# Sheet2.net
KiCad netlist of a schematic drawn in Altium Designer
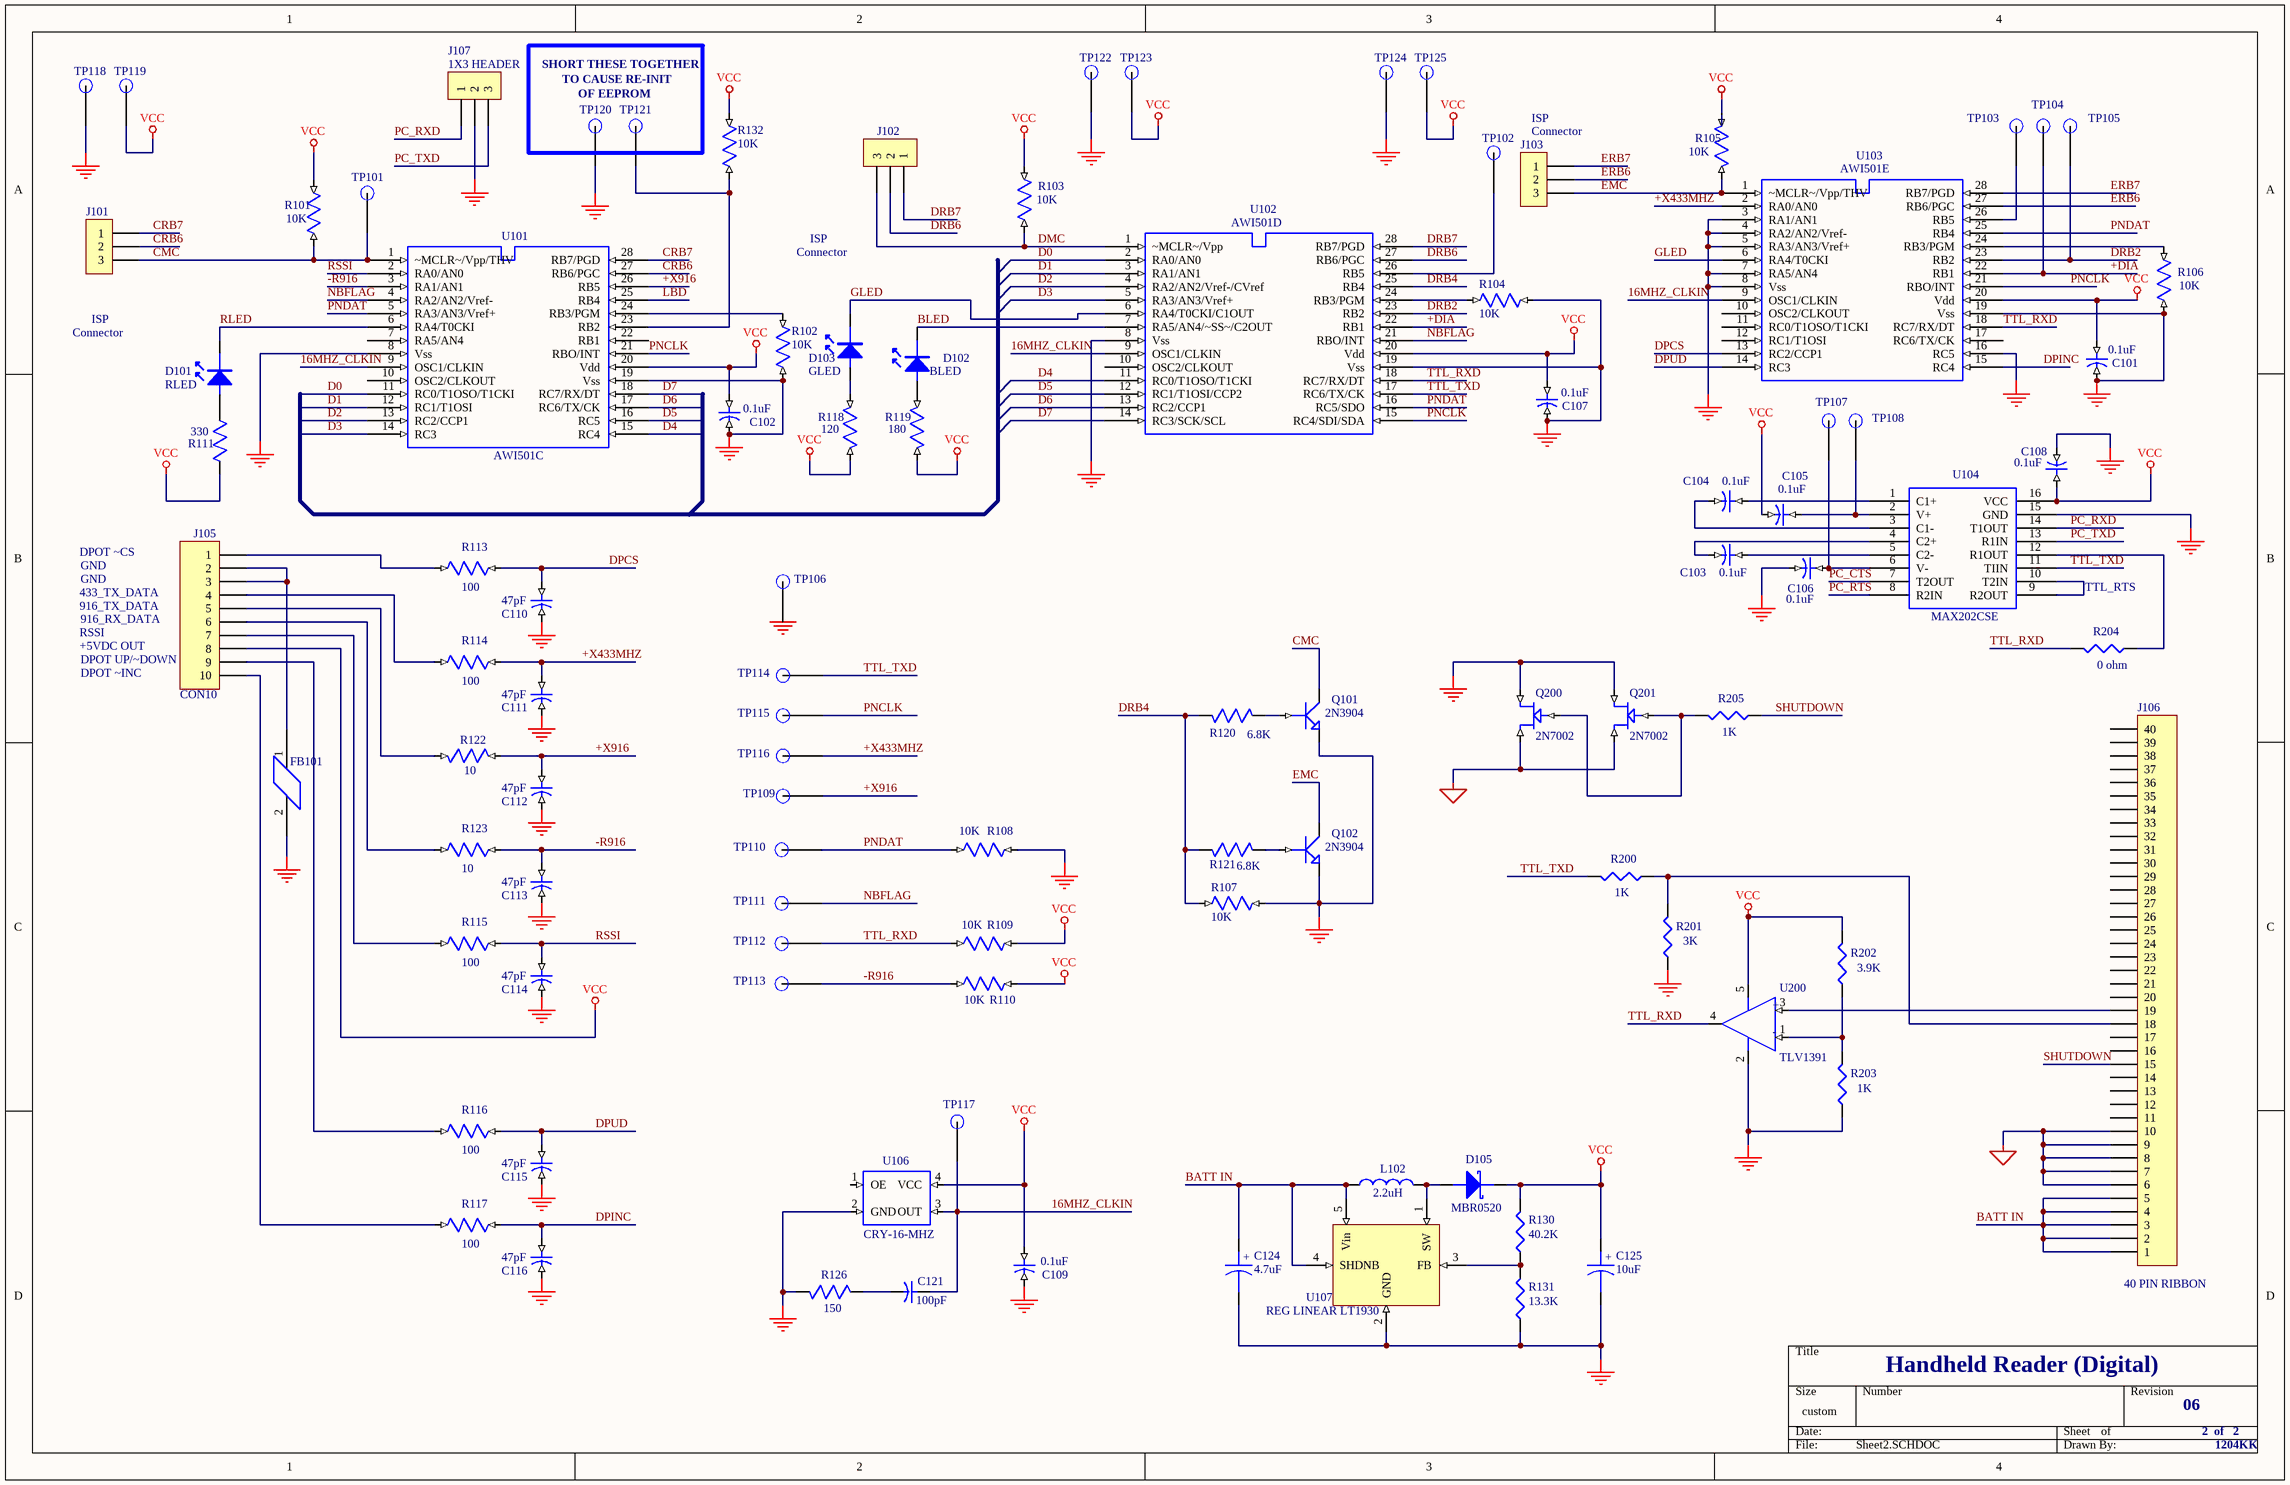
[diagram p0: Sheet2.SCHDOC]

(export (version "E")
  (design (tool "Eeschema 10.0.6"))
  (components
    (comp (ref "C101") (value "0.1uF") (footprint "0603") (libsource (lib "") (part "C_603_1")))
    (comp (ref "C102") (value "0.1uF") (footprint "0603") (libsource (lib "") (part "C_603_1")))
    (comp (ref "C103") (value "0.1uF") (footprint "0603") (libsource (lib "*") (part "C_603")))
    (comp (ref "C104") (value "0.1uF") (footprint "0603") (libsource (lib "*") (part "C_603")))
    (comp (ref "C105") (value "0.1uF") (footprint "0603") (libsource (lib "*") (part "C_603")))
    (comp (ref "C106") (value "0.1uF") (footprint "0603") (libsource (lib "*") (part "C_603")))
    (comp (ref "C107") (value "0.1uF") (footprint "0603") (libsource (lib "") (part "C_603_1")))
    (comp (ref "C108") (value "0.1uF") (footprint "0603") (libsource (lib "*") (part "C_603")))
    (comp (ref "C109") (value "0.1uF") (footprint "0603") (libsource (lib "*") (part "C_603")))
    (comp (ref "C110") (value "47pF") (footprint "0603") (libsource (lib "*") (part "C0603")))
    (comp (ref "C111") (value "47pF") (footprint "0603") (libsource (lib "*") (part "C0603")))
    (comp (ref "C112") (value "47pF") (footprint "0603") (libsource (lib "*") (part "C0603")))
    (comp (ref "C113") (value "47pF") (footprint "0603") (libsource (lib "*") (part "C0603")))
    (comp (ref "C114") (value "47pF") (footprint "0603") (libsource (lib "*") (part "C0603")))
    (comp (ref "C115") (value "47pF") (footprint "0603") (libsource (lib "*") (part "C0603")))
    (comp (ref "C116") (value "47pF") (footprint "0603") (libsource (lib "*") (part "C0603")))
    (comp (ref "C121") (value "100pF") (footprint "0603") (libsource (lib "*") (part "C_0603")))
    (comp (ref "C124")
      (value "4.7uF")
      (footprint "CAP A CASE")
      (description "Capacitor")
      (libsource (lib "*") (part "CAPACITOR POL"))
    )
    (comp (ref "C125")
      (value "10uF")
      (footprint "CAP A CASE")
      (description "Capacitor")
      (libsource (lib "*") (part "CAPACITOR POL"))
    )
    (comp (ref "D101") (value "RLED") (footprint "SOD123 DIODE") (libsource (lib "*") (part "LED")))
    (comp (ref "D102") (value "BLED") (footprint "SOD123 DIODE") (libsource (lib "*") (part "LED")))
    (comp (ref "D103") (value "GLED") (footprint "SOD123 DIODE") (libsource (lib "*") (part "LED")))
    (comp (ref "D105")
      (value "MBR0520")
      (footprint "SOD123")
      (description "Schottky Diode")
      (libsource (lib "*") (part "DIODE SCHOTTKY"))
    )
    (comp (ref "FB101") (value "FB 0603") (footprint "0603") (libsource (lib "*") (part "FB_0603")))
    (comp (ref "J101")
      (value "1X3 HEADER")
      (footprint "1X3 HEADER")
      (description "Connector")
      (libsource (lib "*") (part "CON3"))
    )
    (comp (ref "J102")
      (value "1X3 HEADER")
      (footprint "1X3 HEADER")
      (description "Connector")
      (libsource (lib "") (part "CON3_1"))
    )
    (comp (ref "J103")
      (value "1X3 HEADER")
      (footprint "1X3 HEADER")
      (description "Connector")
      (libsource (lib "*") (part "CON3"))
    )
    (comp (ref "J105")
      (value "CON10")
      (footprint "1X10 HEADER SPECIAL")
      (description "Connector")
      (libsource (lib "*") (part "CON10"))
    )
    (comp (ref "J106")
      (value "40 PIN RIBBON")
      (footprint "40 PIN RIBBON CONN")
      (description "Connector")
      (libsource (lib "*") (part "CON40"))
    )
    (comp (ref "J107")
      (value "1X3 HEADER")
      (footprint "1X3 HEADER")
      (description "Connector")
      (libsource (lib "") (part "CON3_2"))
    )
    (comp (ref "L102")
      (value "2.2uH")
      (footprint "COIL BOURNS SDR7030-330M")
      (libsource (lib "*") (part "INDUCTOR1"))
    )
    (comp (ref "Q101")
      (value "2N3904")
      (footprint "SOT23 TRANS")
      (description "NPN Transistor")
      (libsource (lib "*") (part "NPN1"))
    )
    (comp (ref "Q102")
      (value "2N3904")
      (footprint "SOT23 TRANS")
      (description "NPN Transistor")
      (libsource (lib "*") (part "NPN1"))
    )
    (comp (ref "Q200") (value "2N7002") (footprint "SOT23 FET") (libsource (lib "*") (part "JFET N")))
    (comp (ref "Q201") (value "2N7002") (footprint "SOT23 FET") (libsource (lib "*") (part "JFET N")))
    (comp (ref "R101") (value "10K") (footprint "0603") (libsource (lib "*") (part "R_603")))
    (comp (ref "R102") (value "10K") (footprint "0603") (libsource (lib "*") (part "R_603")))
    (comp (ref "R103") (value "10K") (footprint "0603") (libsource (lib "*") (part "R_603")))
    (comp (ref "R104") (value "10K") (footprint "0603") (libsource (lib "*") (part "R_603")))
    (comp (ref "R105") (value "10K") (footprint "0603") (libsource (lib "*") (part "R_603")))
    (comp (ref "R106") (value "10K") (footprint "0603") (libsource (lib "*") (part "R_603")))
    (comp (ref "R107") (value "10K") (footprint "0603") (libsource (lib "*") (part "R_603")))
    (comp (ref "R108") (value "10K") (footprint "0603") (libsource (lib "*") (part "R_603")))
    (comp (ref "R109") (value "10K") (footprint "0603") (libsource (lib "*") (part "R_603")))
    (comp (ref "R110") (value "10K") (footprint "0603") (libsource (lib "*") (part "R_603")))
    (comp (ref "R111") (value "330") (footprint "0603") (libsource (lib "*") (part "R_0603")))
    (comp (ref "R113") (value "100") (footprint "0603") (libsource (lib "*") (part "R0603")))
    (comp (ref "R114") (value "100") (footprint "0603") (libsource (lib "*") (part "R0603")))
    (comp (ref "R115") (value "100") (footprint "0603") (libsource (lib "*") (part "R0603")))
    (comp (ref "R116") (value "100") (footprint "0603") (libsource (lib "*") (part "R0603")))
    (comp (ref "R117") (value "100") (footprint "0603") (libsource (lib "*") (part "R0603")))
    (comp (ref "R118") (value "120") (footprint "0603") (libsource (lib "*") (part "R0402")))
    (comp (ref "R119") (value "180") (footprint "0603") (libsource (lib "*") (part "R0402")))
    (comp (ref "R120") (value "6.8K") (footprint "0603") (libsource (lib "*") (part "R_0603")))
    (comp (ref "R121") (value "6.8K") (footprint "0603") (libsource (lib "*") (part "R_0603")))
    (comp (ref "R122") (value "10") (footprint "0603") (libsource (lib "*") (part "R_603")))
    (comp (ref "R123") (value "10") (footprint "0603") (libsource (lib "*") (part "R0603")))
    (comp (ref "R126") (value "150") (footprint "0603") (libsource (lib "*") (part "R_0603")))
    (comp (ref "R130") (value "40.2K") (footprint "0603") (libsource (lib "*") (part "RES1")))
    (comp (ref "R131") (value "13.3K") (footprint "0603") (libsource (lib "*") (part "RES1")))
    (comp (ref "R132") (value "10K") (footprint "0603") (libsource (lib "*") (part "R_603")))
    (comp (ref "R200") (value "1K") (footprint "0603") (libsource (lib "*") (part "RES1")))
    (comp (ref "R201") (value "3K") (footprint "0603") (libsource (lib "*") (part "RES1")))
    (comp (ref "R202") (value "3.9K") (footprint "0603") (libsource (lib "*") (part "RES1")))
    (comp (ref "R203") (value "1K") (footprint "0603") (libsource (lib "*") (part "RES1")))
    (comp (ref "R204") (value "0 ohm") (footprint "0603") (libsource (lib "*") (part "RES1")))
    (comp (ref "R205") (value "1K") (footprint "0603") (libsource (lib "*") (part "RES1")))
    (comp (ref "TP101") (value "TP") (footprint "TEST POINT PAD") (libsource (lib "*") (part "TESTPOINT_1")))
    (comp (ref "TP102") (value "TP") (footprint "TEST POINT PAD") (libsource (lib "*") (part "TESTPOINT_1")))
    (comp (ref "TP103") (value "TP") (footprint "TEST POINT PAD") (libsource (lib "*") (part "TESTPOINT_1")))
    (comp (ref "TP104") (value "TP") (footprint "TEST POINT PAD") (libsource (lib "*") (part "TESTPOINT_1")))
    (comp (ref "TP105") (value "TP") (footprint "TEST POINT PAD") (libsource (lib "*") (part "TESTPOINT_1")))
    (comp (ref "TP106") (value "TP") (footprint "TEST POINT PAD") (libsource (lib "*") (part "TESTPOINT_1")))
    (comp (ref "TP107") (value "TP") (footprint "TEST POINT PAD") (libsource (lib "*") (part "TESTPOINT_1")))
    (comp (ref "TP108") (value "TP") (footprint "TEST POINT PAD") (libsource (lib "*") (part "TESTPOINT_1")))
    (comp (ref "TP109") (value "TP") (footprint "TEST POINT PAD") (libsource (lib "*") (part "TESTPOINT_1")))
    (comp (ref "TP110") (value "TP") (footprint "TEST POINT PAD") (libsource (lib "*") (part "TESTPOINT_1")))
    (comp (ref "TP111") (value "TP") (footprint "TEST POINT PAD") (libsource (lib "*") (part "TESTPOINT_1")))
    (comp (ref "TP112") (value "TP") (footprint "TEST POINT PAD") (libsource (lib "*") (part "TESTPOINT_1")))
    (comp (ref "TP113") (value "TP") (footprint "TEST POINT PAD") (libsource (lib "*") (part "TESTPOINT_1")))
    (comp (ref "TP114") (value "TP") (footprint "TEST POINT PAD") (libsource (lib "*") (part "TESTPOINT_1")))
    (comp (ref "TP115") (value "TP") (footprint "TEST POINT PAD") (libsource (lib "*") (part "TESTPOINT_1")))
    (comp (ref "TP116") (value "TP") (footprint "TEST POINT PAD") (libsource (lib "*") (part "TESTPOINT_1")))
    (comp (ref "TP117") (value "TP") (footprint "TEST POINT PAD") (libsource (lib "*") (part "TESTPOINT_1")))
    (comp (ref "TP118") (value "TP") (footprint "TEST POINT PAD") (libsource (lib "*") (part "TESTPOINT_1")))
    (comp (ref "TP119") (value "TP") (footprint "TEST POINT PAD") (libsource (lib "*") (part "TESTPOINT_1")))
    (comp (ref "TP120") (value "TP") (footprint "TEST POINT PAD") (libsource (lib "*") (part "TESTPOINT_1")))
    (comp (ref "TP121") (value "TP") (footprint "TEST POINT PAD") (libsource (lib "*") (part "TESTPOINT_1")))
    (comp (ref "TP122") (value "TP") (footprint "TEST POINT PAD") (libsource (lib "*") (part "TESTPOINT_1")))
    (comp (ref "TP123") (value "TP") (footprint "TEST POINT PAD") (libsource (lib "*") (part "TESTPOINT_1")))
    (comp (ref "TP124") (value "TP") (footprint "TEST POINT PAD") (libsource (lib "*") (part "TESTPOINT_1")))
    (comp (ref "TP125") (value "TP") (footprint "TEST POINT PAD") (libsource (lib "*") (part "TESTPOINT_1")))
    (comp (ref "U101") (value "AWI501C") (footprint "SSOP28") (libsource (lib "*") (part "PIC16F870")))
    (comp (ref "U102") (value "AWI501D") (footprint "SSOP28") (libsource (lib "*") (part "PIC16F876A")))
    (comp (ref "U103") (value "AWI501E") (footprint "SSOP28") (libsource (lib "*") (part "PIC16F870")))
    (comp (ref "U104") (value "MAX202CSE") (footprint "SO16") (libsource (lib "*") (part "MAX202CSE")))
    (comp (ref "U106")
      (value "CRY-16-MHZ")
      (footprint "SMT OSCILLATOR")
      (libsource (lib "*") (part "CRY-SMD-5-7"))
    )
    (comp (ref "U107")
      (value "REG LINEAR LT1930")
      (footprint "SOT23-5A")
      (libsource (lib "*") (part "REG LINEAR LT1930"))
    )
    (comp (ref "U200") (value "TLV1391") (footprint "SOT25") (libsource (lib "*") (part "TLV1391")))
  )
  (nets
    (net (code "1") (name "/+DIA") (class "Default")
      (node (ref "TP104") (pin "1") (pinfunction "TP_1") (pintype "passive"))
      (node (ref "U102") (pin "22") (pinfunction "RB1_22") (pintype "input"))
      (node (ref "U103") (pin "22") (pinfunction "RB1_22") (pintype "input"))
    )
    (net (code "2") (name "/+X433MHZ") (class "Default")
      (node (ref "C111") (pin "1") (pinfunction "A_1") (pintype "input"))
      (node (ref "R114") (pin "2") (pinfunction "B_2") (pintype "input"))
      (node (ref "TP116") (pin "1") (pinfunction "TP_1") (pintype "passive"))
      (node (ref "U103") (pin "2") (pinfunction "RA0/AN0_2") (pintype "input"))
    )
    (net (code "3") (name "/+X916") (class "Default")
      (node (ref "C112") (pin "1") (pinfunction "A_1") (pintype "input"))
      (node (ref "R122") (pin "1") (pinfunction "A_1") (pintype "input"))
      (node (ref "TP109") (pin "1") (pinfunction "TP_1") (pintype "passive"))
      (node (ref "U101") (pin "26") (pinfunction "RB5_26") (pintype "input"))
    )
    (net (code "4") (name "/-R916") (class "Default")
      (node (ref "C113") (pin "1") (pinfunction "A_1") (pintype "input"))
      (node (ref "R110") (pin "2") (pinfunction "B_2") (pintype "input"))
      (node (ref "R123") (pin "2") (pinfunction "B_2") (pintype "input"))
      (node (ref "TP113") (pin "1") (pinfunction "TP_1") (pintype "passive"))
      (node (ref "U101") (pin "3") (pinfunction "RA1/AN1_3") (pintype "input"))
    )
    (net (code "5") (name "/16MHZ_CLKIN") (class "Default")
      (node (ref "C121") (pin "1") (pinfunction "A_1") (pintype "passive"))
      (node (ref "TP117") (pin "1") (pinfunction "TP_1") (pintype "passive"))
      (node (ref "U101") (pin "9") (pinfunction "OSC1/CLKIN_9") (pintype "input"))
      (node (ref "U102") (pin "9") (pinfunction "OSC1/CLKIN_9") (pintype "input"))
      (node (ref "U103") (pin "9") (pinfunction "OSC1/CLKIN_9") (pintype "input"))
      (node (ref "U106") (pin "3") (pinfunction "OUT_3") (pintype "input"))
    )
    (net (code "6") (name "/BATT IN") (class "Default")
      (node (ref "C124") (pin "1") (pinfunction "1_1") (pintype "passive"))
      (node (ref "J106") (pin "1") (pinfunction "1_1") (pintype "passive"))
      (node (ref "J106") (pin "2") (pinfunction "2_2") (pintype "passive"))
      (node (ref "J106") (pin "3") (pinfunction "3_3") (pintype "passive"))
      (node (ref "J106") (pin "4") (pinfunction "4_4") (pintype "passive"))
      (node (ref "J106") (pin "5") (pinfunction "5_5") (pintype "passive"))
      (node (ref "L102") (pin "1") (pinfunction "1_1") (pintype "passive"))
      (node (ref "U107") (pin "4") (pinfunction "SHDNB_4") (pintype "input"))
      (node (ref "U107") (pin "5") (pinfunction "Vin_5") (pintype "input"))
    )
    (net (code "7") (name "/BLED") (class "Default")
      (node (ref "D102") (pin "K") (pinfunction "K_K") (pintype "passive"))
      (node (ref "U102") (pin "7") (pinfunction "RA5/AN4/~SS~/C2OUT_7") (pintype "input"))
    )
    (net (code "8") (name "/CMC") (class "Default")
      (node (ref "J101") (pin "3") (pinfunction "3_3") (pintype "passive"))
      (node (ref "Q101") (pin "C") (pinfunction "C_C") (pintype "passive"))
      (node (ref "R101") (pin "2") (pinfunction "B_2") (pintype "input"))
      (node (ref "TP101") (pin "1") (pinfunction "TP_1") (pintype "passive"))
      (node (ref "U101") (pin "1") (pinfunction "~MCLR~/Vpp/THV_1") (pintype "input"))
    )
    (net (code "9") (name "/CRB6") (class "Default")
      (node (ref "J101") (pin "2") (pinfunction "2_2") (pintype "passive"))
      (node (ref "U101") (pin "27") (pinfunction "RB6/PGC_27") (pintype "input"))
    )
    (net (code "10") (name "/CRB7") (class "Default")
      (node (ref "J101") (pin "1") (pinfunction "1_1") (pintype "passive"))
      (node (ref "U101") (pin "28") (pinfunction "RB7/PGD_28") (pintype "input"))
    )
    (net (code "11") (name "/D0") (class "Default")
      (node (ref "U101") (pin "11") (pinfunction "RC0/T1OSO/T1CKI_11") (pintype "input"))
      (node (ref "U102") (pin "2") (pinfunction "RA0/AN0_2") (pintype "input"))
    )
    (net (code "12") (name "/D1") (class "Default")
      (node (ref "U101") (pin "12") (pinfunction "RC1/T1OSI_12") (pintype "input"))
      (node (ref "U102") (pin "3") (pinfunction "RA1/AN1_3") (pintype "input"))
    )
    (net (code "13") (name "/D2") (class "Default")
      (node (ref "U101") (pin "13") (pinfunction "RC2/CCP1_13") (pintype "input"))
      (node (ref "U102") (pin "4") (pinfunction "RA2/AN2/Vref-/CVref_4") (pintype "input"))
    )
    (net (code "14") (name "/D3") (class "Default")
      (node (ref "U101") (pin "14") (pinfunction "RC3_14") (pintype "input"))
      (node (ref "U102") (pin "5") (pinfunction "RA3/AN3/Vref+_5") (pintype "input"))
    )
    (net (code "15") (name "/D4") (class "Default")
      (node (ref "U101") (pin "15") (pinfunction "RC4_15") (pintype "input"))
      (node (ref "U102") (pin "11") (pinfunction "RC0/T1OSO/T1CKI_11") (pintype "input"))
    )
    (net (code "16") (name "/D5") (class "Default")
      (node (ref "U101") (pin "16") (pinfunction "RC5_16") (pintype "input"))
      (node (ref "U102") (pin "12") (pinfunction "RC1/T1OSI/CCP2_12") (pintype "input"))
    )
    (net (code "17") (name "/D6") (class "Default")
      (node (ref "U101") (pin "17") (pinfunction "RC6/TX/CK_17") (pintype "input"))
      (node (ref "U102") (pin "13") (pinfunction "RC2/CCP1_13") (pintype "input"))
    )
    (net (code "18") (name "/D7") (class "Default")
      (node (ref "U101") (pin "18") (pinfunction "RC7/RX/DT_18") (pintype "input"))
      (node (ref "U102") (pin "14") (pinfunction "RC3/SCK/SCL_14") (pintype "input"))
    )
    (net (code "19") (name "/DMC") (class "Default")
      (node (ref "J102") (pin "3") (pinfunction "3_3") (pintype "passive"))
      (node (ref "R103") (pin "2") (pinfunction "B_2") (pintype "input"))
      (node (ref "U102") (pin "1") (pinfunction "~MCLR~/Vpp_1") (pintype "input"))
    )
    (net (code "20") (name "/DPCS") (class "Default")
      (node (ref "C110") (pin "1") (pinfunction "A_1") (pintype "input"))
      (node (ref "R113") (pin "2") (pinfunction "B_2") (pintype "input"))
      (node (ref "U103") (pin "13") (pinfunction "RC2/CCP1_13") (pintype "input"))
    )
    (net (code "21") (name "/DPINC") (class "Default")
      (node (ref "C116") (pin "1") (pinfunction "A_1") (pintype "input"))
      (node (ref "R117") (pin "2") (pinfunction "B_2") (pintype "input"))
      (node (ref "U103") (pin "15") (pinfunction "RC4_15") (pintype "input"))
    )
    (net (code "22") (name "/DPUD") (class "Default")
      (node (ref "C115") (pin "1") (pinfunction "A_1") (pintype "input"))
      (node (ref "R116") (pin "2") (pinfunction "B_2") (pintype "input"))
      (node (ref "U103") (pin "14") (pinfunction "RC3_14") (pintype "input"))
    )
    (net (code "23") (name "/DRB2") (class "Default")
      (node (ref "TP105") (pin "1") (pinfunction "TP_1") (pintype "passive"))
      (node (ref "U102") (pin "23") (pinfunction "RB2_23") (pintype "input"))
      (node (ref "U103") (pin "23") (pinfunction "RB2_23") (pintype "input"))
    )
    (net (code "24") (name "/DRB4") (class "Default")
      (node (ref "R107") (pin "1") (pinfunction "A_1") (pintype "input"))
      (node (ref "R120") (pin "1") (pinfunction "A_1") (pintype "passive"))
      (node (ref "R121") (pin "1") (pinfunction "A_1") (pintype "passive"))
      (node (ref "U102") (pin "25") (pinfunction "RB4_25") (pintype "input"))
    )
    (net (code "25") (name "/DRB6") (class "Default")
      (node (ref "J102") (pin "2") (pinfunction "2_2") (pintype "passive"))
      (node (ref "U102") (pin "27") (pinfunction "RB6/PGC_27") (pintype "input"))
    )
    (net (code "26") (name "/DRB7") (class "Default")
      (node (ref "J102") (pin "1") (pinfunction "1_1") (pintype "passive"))
      (node (ref "U102") (pin "28") (pinfunction "RB7/PGD_28") (pintype "input"))
    )
    (net (code "27") (name "/EMC") (class "Default")
      (node (ref "J103") (pin "3") (pinfunction "3_3") (pintype "passive"))
      (node (ref "Q102") (pin "C") (pinfunction "C_C") (pintype "passive"))
      (node (ref "R105") (pin "2") (pinfunction "B_2") (pintype "input"))
      (node (ref "U103") (pin "1") (pinfunction "~MCLR~/Vpp/THV_1") (pintype "input"))
    )
    (net (code "28") (name "/ERB6") (class "Default")
      (node (ref "J103") (pin "2") (pinfunction "2_2") (pintype "passive"))
      (node (ref "U103") (pin "27") (pinfunction "RB6/PGC_27") (pintype "input"))
    )
    (net (code "29") (name "/ERB7") (class "Default")
      (node (ref "J103") (pin "1") (pinfunction "1_1") (pintype "passive"))
      (node (ref "U103") (pin "28") (pinfunction "RB7/PGD_28") (pintype "input"))
    )
    (net (code "30") (name "/GLED") (class "Default")
      (node (ref "D103") (pin "K") (pinfunction "K_K") (pintype "passive"))
      (node (ref "U102") (pin "6") (pinfunction "RA4/T0CKI/C1OUT_6") (pintype "input"))
      (node (ref "U103") (pin "6") (pinfunction "RA4/T0CKI_6") (pintype "input"))
    )
    (net (code "31") (name "/LBD") (class "Default")
      (node (ref "U101") (pin "25") (pinfunction "RB4_25") (pintype "input"))
    )
    (net (code "32") (name "/NBFLAG") (class "Default")
      (node (ref "TP111") (pin "1") (pinfunction "TP_1") (pintype "passive"))
      (node (ref "U101") (pin "4") (pinfunction "RA2/AN2/Vref-_4") (pintype "input"))
      (node (ref "U102") (pin "21") (pinfunction "RBO/INT_21") (pintype "input"))
    )
    (net (code "33") (name "/PC_CTS") (class "Default")
      (node (ref "U104") (pin "7") (pinfunction "T2OUT_7") (pintype "passive"))
    )
    (net (code "34") (name "/PC_RTS") (class "Default")
      (node (ref "U104") (pin "8") (pinfunction "R2IN_8") (pintype "passive"))
    )
    (net (code "35") (name "/PC_RXD") (class "Default")
      (node (ref "J107") (pin "1") (pinfunction "1_1") (pintype "passive"))
      (node (ref "U104") (pin "14") (pinfunction "T1OUT_14") (pintype "passive"))
    )
    (net (code "36") (name "/PC_TXD") (class "Default")
      (node (ref "J107") (pin "3") (pinfunction "3_3") (pintype "passive"))
      (node (ref "U104") (pin "13") (pinfunction "R1IN_13") (pintype "passive"))
    )
    (net (code "37") (name "/PNCLK") (class "Default")
      (node (ref "TP115") (pin "1") (pinfunction "TP_1") (pintype "passive"))
      (node (ref "U101") (pin "21") (pinfunction "RBO/INT_21") (pintype "input"))
      (node (ref "U102") (pin "15") (pinfunction "RC4/SDI/SDA_15") (pintype "input"))
      (node (ref "U103") (pin "21") (pinfunction "RBO/INT_21") (pintype "input"))
    )
    (net (code "38") (name "/PNDAT") (class "Default")
      (node (ref "R108") (pin "2") (pinfunction "B_2") (pintype "input"))
      (node (ref "TP110") (pin "1") (pinfunction "TP_1") (pintype "passive"))
      (node (ref "U101") (pin "5") (pinfunction "RA3/AN3/Vref+_5") (pintype "input"))
      (node (ref "U102") (pin "16") (pinfunction "RC5/SDO_16") (pintype "input"))
      (node (ref "U103") (pin "25") (pinfunction "RB4_25") (pintype "input"))
    )
    (net (code "39") (name "/RLED") (class "Default")
      (node (ref "D101") (pin "K") (pinfunction "K_K") (pintype "passive"))
      (node (ref "U101") (pin "6") (pinfunction "RA4/T0CKI_6") (pintype "input"))
    )
    (net (code "40") (name "/RSSI") (class "Default")
      (node (ref "C114") (pin "1") (pinfunction "A_1") (pintype "input"))
      (node (ref "R115") (pin "2") (pinfunction "B_2") (pintype "input"))
      (node (ref "U101") (pin "2") (pinfunction "RA0/AN0_2") (pintype "input"))
    )
    (net (code "41") (name "/SHUTDOWN") (class "Default")
      (node (ref "J106") (pin "15") (pinfunction "15_15") (pintype "passive"))
      (node (ref "R205") (pin "1") (pinfunction "1_1") (pintype "passive"))
    )
    (net (code "42") (name "/TTL_RXD") (class "Default")
      (node (ref "R109") (pin "2") (pinfunction "B_2") (pintype "input"))
      (node (ref "R204") (pin "2") (pinfunction "2_2") (pintype "passive"))
      (node (ref "TP112") (pin "1") (pinfunction "TP_1") (pintype "passive"))
      (node (ref "U102") (pin "18") (pinfunction "RC7/RX/DT_18") (pintype "input"))
      (node (ref "U103") (pin "18") (pinfunction "RC7/RX/DT_18") (pintype "input"))
      (node (ref "U200") (pin "4") (pinfunction "OUT_4") (pintype "open_collector"))
    )
    (net (code "43") (name "/TTL_TXD") (class "Default")
      (node (ref "R200") (pin "2") (pinfunction "2_2") (pintype "passive"))
      (node (ref "TP114") (pin "1") (pinfunction "TP_1") (pintype "passive"))
      (node (ref "U102") (pin "17") (pinfunction "RC6/TX/CK_17") (pintype "input"))
      (node (ref "U104") (pin "11") (pinfunction "TIIN_11") (pintype "passive"))
    )
    (net (code "44") (name "GND1") (class "Default")
      (node (ref "J106") (pin "10") (pinfunction "10_10") (pintype "passive"))
      (node (ref "J106") (pin "6") (pinfunction "6_6") (pintype "passive"))
      (node (ref "J106") (pin "7") (pinfunction "7_7") (pintype "passive"))
      (node (ref "J106") (pin "8") (pinfunction "8_8") (pintype "passive"))
      (node (ref "J106") (pin "9") (pinfunction "9_9") (pintype "passive"))
      (node (ref "Q200") (pin "S") (pinfunction "S_S") (pintype "input"))
      (node (ref "Q201") (pin "S") (pinfunction "S_S") (pintype "input"))
    )
    (net (code "45") (name "GND_COM") (class "Default")
      (node (ref "C101") (pin "2") (pinfunction "B_2") (pintype "input"))
      (node (ref "C102") (pin "2") (pinfunction "B_2") (pintype "input"))
      (node (ref "C106") (pin "2") (pinfunction "B_2") (pintype "input"))
      (node (ref "C107") (pin "2") (pinfunction "B_2") (pintype "input"))
      (node (ref "C108") (pin "2") (pinfunction "B_2") (pintype "input"))
      (node (ref "C109") (pin "2") (pinfunction "B_2") (pintype "input"))
      (node (ref "C110") (pin "2") (pinfunction "B_2") (pintype "input"))
      (node (ref "C111") (pin "2") (pinfunction "B_2") (pintype "input"))
      (node (ref "C112") (pin "2") (pinfunction "B_2") (pintype "input"))
      (node (ref "C113") (pin "2") (pinfunction "B_2") (pintype "input"))
      (node (ref "C114") (pin "2") (pinfunction "B_2") (pintype "input"))
      (node (ref "C115") (pin "2") (pinfunction "B_2") (pintype "input"))
      (node (ref "C116") (pin "2") (pinfunction "B_2") (pintype "input"))
      (node (ref "C124") (pin "2") (pinfunction "2_2") (pintype "passive"))
      (node (ref "C125") (pin "2") (pinfunction "2_2") (pintype "passive"))
      (node (ref "FB101") (pin "2") (pinfunction "1_2") (pintype "passive"))
      (node (ref "J107") (pin "2") (pinfunction "2_2") (pintype "passive"))
      (node (ref "Q101") (pin "E") (pinfunction "E_E") (pintype "passive"))
      (node (ref "Q102") (pin "E") (pinfunction "E_E") (pintype "passive"))
      (node (ref "Q200") (pin "D") (pinfunction "D_D") (pintype "input"))
      (node (ref "Q201") (pin "D") (pinfunction "D_D") (pintype "input"))
      (node (ref "R102") (pin "2") (pinfunction "B_2") (pintype "input"))
      (node (ref "R104") (pin "1") (pinfunction "A_1") (pintype "input"))
      (node (ref "R106") (pin "2") (pinfunction "B_2") (pintype "input"))
      (node (ref "R107") (pin "2") (pinfunction "B_2") (pintype "input"))
      (node (ref "R108") (pin "1") (pinfunction "A_1") (pintype "input"))
      (node (ref "R126") (pin "2") (pinfunction "B_2") (pintype "passive"))
      (node (ref "R131") (pin "1") (pinfunction "1_1") (pintype "passive"))
      (node (ref "R201") (pin "1") (pinfunction "1_1") (pintype "passive"))
      (node (ref "R203") (pin "1") (pinfunction "1_1") (pintype "passive"))
      (node (ref "TP106") (pin "1") (pinfunction "TP_1") (pintype "passive"))
      (node (ref "TP118") (pin "1") (pinfunction "TP_1") (pintype "passive"))
      (node (ref "TP120") (pin "1") (pinfunction "TP_1") (pintype "passive"))
      (node (ref "TP122") (pin "1") (pinfunction "TP_1") (pintype "passive"))
      (node (ref "TP124") (pin "1") (pinfunction "TP_1") (pintype "passive"))
      (node (ref "U101") (pin "19") (pinfunction "Vss_19") (pintype "input"))
      (node (ref "U101") (pin "8") (pinfunction "Vss_8") (pintype "input"))
      (node (ref "U102") (pin "19") (pinfunction "Vss_19") (pintype "input"))
      (node (ref "U102") (pin "8") (pinfunction "Vss_8") (pintype "input"))
      (node (ref "U103") (pin "16") (pinfunction "RC5_16") (pintype "input"))
      (node (ref "U103") (pin "19") (pinfunction "Vss_19") (pintype "input"))
      (node (ref "U103") (pin "3") (pinfunction "RA1/AN1_3") (pintype "input"))
      (node (ref "U103") (pin "4") (pinfunction "RA2/AN2/Vref-_4") (pintype "input"))
      (node (ref "U103") (pin "5") (pinfunction "RA3/AN3/Vref+_5") (pintype "input"))
      (node (ref "U103") (pin "7") (pinfunction "RA5/AN4_7") (pintype "input"))
      (node (ref "U103") (pin "8") (pinfunction "Vss_8") (pintype "input"))
      (node (ref "U104") (pin "15") (pinfunction "GND_15") (pintype "passive"))
      (node (ref "U106") (pin "2") (pinfunction "GND_2") (pintype "input"))
      (node (ref "U107") (pin "2") (pinfunction "GND_2") (pintype "input"))
      (node (ref "U200") (pin "2") (pinfunction "VSS_2") (pintype "power_in"))
    )
    (net (code "46") (name "Net-(C103-A)") (class "Default")
      (node (ref "C103") (pin "1") (pinfunction "A_1") (pintype "input"))
      (node (ref "U104") (pin "5") (pinfunction "C2-_5") (pintype "passive"))
    )
    (net (code "47") (name "Net-(C103-B)") (class "Default")
      (node (ref "C103") (pin "2") (pinfunction "B_2") (pintype "input"))
      (node (ref "U104") (pin "4") (pinfunction "C2+_4") (pintype "passive"))
    )
    (net (code "48") (name "Net-(C104-A)") (class "Default")
      (node (ref "C104") (pin "1") (pinfunction "A_1") (pintype "input"))
      (node (ref "U104") (pin "1") (pinfunction "C1+_1") (pintype "passive"))
    )
    (net (code "49") (name "Net-(C104-B)") (class "Default")
      (node (ref "C104") (pin "2") (pinfunction "B_2") (pintype "input"))
      (node (ref "U104") (pin "3") (pinfunction "C1-_3") (pintype "passive"))
    )
    (net (code "50") (name "Net-(C105-A)") (class "Default")
      (node (ref "C105") (pin "1") (pinfunction "A_1") (pintype "input"))
      (node (ref "TP108") (pin "1") (pinfunction "TP_1") (pintype "passive"))
      (node (ref "U104") (pin "2") (pinfunction "V+_2") (pintype "passive"))
    )
    (net (code "51") (name "Net-(C106-A)") (class "Default")
      (node (ref "C106") (pin "1") (pinfunction "A_1") (pintype "input"))
      (node (ref "TP107") (pin "1") (pinfunction "TP_1") (pintype "passive"))
      (node (ref "U104") (pin "6") (pinfunction "V-_6") (pintype "passive"))
    )
    (net (code "52") (name "Net-(C121-B)") (class "Default")
      (node (ref "C121") (pin "2") (pinfunction "B_2") (pintype "passive"))
      (node (ref "R126") (pin "1") (pinfunction "A_1") (pintype "passive"))
    )
    (net (code "53") (name "Net-(FB101-2)") (class "Default")
      (node (ref "FB101") (pin "1") (pinfunction "2_1") (pintype "passive"))
      (node (ref "J105") (pin "2") (pinfunction "2_2") (pintype "passive"))
      (node (ref "J105") (pin "3") (pinfunction "3_3") (pintype "passive"))
    )
    (net (code "54") (name "Net-(J106-Pad18)") (class "Default")
      (node (ref "J106") (pin "18") (pinfunction "18_18") (pintype "passive"))
      (node (ref "R200") (pin "1") (pinfunction "1_1") (pintype "passive"))
      (node (ref "R201") (pin "2") (pinfunction "2_2") (pintype "passive"))
    )
    (net (code "55") (name "Net-(Q200-PadG)") (class "Default")
      (node (ref "Q200") (pin "G") (pinfunction "G_G") (pintype "input"))
      (node (ref "Q201") (pin "G") (pinfunction "G_G") (pintype "input"))
      (node (ref "R205") (pin "2") (pinfunction "2_2") (pintype "passive"))
    )
    (net (code "56") (name "Net-(R102-A)") (class "Default")
      (node (ref "R102") (pin "1") (pinfunction "A_1") (pintype "input"))
      (node (ref "U101") (pin "24") (pinfunction "RB3/PGM_24") (pintype "input"))
    )
    (net (code "57") (name "Net-(R104-B)") (class "Default")
      (node (ref "R104") (pin "2") (pinfunction "B_2") (pintype "input"))
      (node (ref "U102") (pin "24") (pinfunction "RB3/PGM_24") (pintype "input"))
    )
    (net (code "58") (name "Net-(R106-A)") (class "Default")
      (node (ref "R106") (pin "1") (pinfunction "A_1") (pintype "input"))
      (node (ref "U103") (pin "24") (pinfunction "RB3/PGM_24") (pintype "input"))
    )
    (net (code "59") (name "Net-(R111-B)") (class "Default")
      (node (ref "D101") (pin "A") (pinfunction "A_A") (pintype "passive"))
      (node (ref "R111") (pin "2") (pinfunction "B_2") (pintype "passive"))
    )
    (net (code "60") (name "Net-(R113-A)") (class "Default")
      (node (ref "J105") (pin "1") (pinfunction "1_1") (pintype "passive"))
      (node (ref "R113") (pin "1") (pinfunction "A_1") (pintype "input"))
    )
    (net (code "61") (name "Net-(R114-A)") (class "Default")
      (node (ref "J105") (pin "4") (pinfunction "4_4") (pintype "passive"))
      (node (ref "R114") (pin "1") (pinfunction "A_1") (pintype "input"))
    )
    (net (code "62") (name "Net-(R115-A)") (class "Default")
      (node (ref "J105") (pin "7") (pinfunction "7_7") (pintype "passive"))
      (node (ref "R115") (pin "1") (pinfunction "A_1") (pintype "input"))
    )
    (net (code "63") (name "Net-(R116-A)") (class "Default")
      (node (ref "J105") (pin "9") (pinfunction "9_9") (pintype "passive"))
      (node (ref "R116") (pin "1") (pinfunction "A_1") (pintype "input"))
    )
    (net (code "64") (name "Net-(R117-A)") (class "Default")
      (node (ref "J105") (pin "10") (pinfunction "10_10") (pintype "passive"))
      (node (ref "R117") (pin "1") (pinfunction "A_1") (pintype "input"))
    )
    (net (code "65") (name "Net-(R118-B)") (class "Default")
      (node (ref "D103") (pin "A") (pinfunction "A_A") (pintype "passive"))
      (node (ref "R118") (pin "2") (pinfunction "B_2") (pintype "input"))
    )
    (net (code "66") (name "Net-(R119-B)") (class "Default")
      (node (ref "D102") (pin "A") (pinfunction "A_A") (pintype "passive"))
      (node (ref "R119") (pin "2") (pinfunction "B_2") (pintype "input"))
    )
    (net (code "67") (name "Net-(R120-B)") (class "Default")
      (node (ref "Q101") (pin "B") (pinfunction "B_B") (pintype "input"))
      (node (ref "R120") (pin "2") (pinfunction "B_2") (pintype "passive"))
    )
    (net (code "68") (name "Net-(R121-B)") (class "Default")
      (node (ref "Q102") (pin "B") (pinfunction "B_B") (pintype "input"))
      (node (ref "R121") (pin "2") (pinfunction "B_2") (pintype "passive"))
    )
    (net (code "69") (name "Net-(R122-B)") (class "Default")
      (node (ref "J105") (pin "5") (pinfunction "5_5") (pintype "passive"))
      (node (ref "R122") (pin "2") (pinfunction "B_2") (pintype "input"))
    )
    (net (code "70") (name "Net-(R123-A)") (class "Default")
      (node (ref "J105") (pin "6") (pinfunction "6_6") (pintype "passive"))
      (node (ref "R123") (pin "1") (pinfunction "A_1") (pintype "input"))
    )
    (net (code "71") (name "Net-(R132-B)") (class "Default")
      (node (ref "R132") (pin "2") (pinfunction "B_2") (pintype "input"))
      (node (ref "TP121") (pin "1") (pinfunction "TP_1") (pintype "passive"))
      (node (ref "U101") (pin "23") (pinfunction "RB2_23") (pintype "input"))
    )
    (net (code "72") (name "Net-(TP102-TP)") (class "Default")
      (node (ref "TP102") (pin "1") (pinfunction "TP_1") (pintype "passive"))
      (node (ref "U102") (pin "26") (pinfunction "RB5_26") (pintype "input"))
    )
    (net (code "73") (name "Net-(TP103-TP)") (class "Default")
      (node (ref "TP103") (pin "1") (pinfunction "TP_1") (pintype "passive"))
      (node (ref "U103") (pin "26") (pinfunction "RB5_26") (pintype "input"))
    )
    (net (code "74") (name "Net-(U104-R1OUT)") (class "Default")
      (node (ref "R204") (pin "1") (pinfunction "1_1") (pintype "passive"))
      (node (ref "U104") (pin "12") (pinfunction "R1OUT_12") (pintype "passive"))
    )
    (net (code "75") (name "Net-(U104-R2OUT)") (class "Default")
      (node (ref "U104") (pin "10") (pinfunction "T2IN_10") (pintype "passive"))
      (node (ref "U104") (pin "9") (pinfunction "R2OUT_9") (pintype "passive"))
    )
    (net (code "76") (name "Net-(U107-FB)") (class "Default")
      (node (ref "R130") (pin "1") (pinfunction "1_1") (pintype "passive"))
      (node (ref "R131") (pin "2") (pinfunction "2_2") (pintype "passive"))
      (node (ref "U107") (pin "3") (pinfunction "FB_3") (pintype "input"))
    )
    (net (code "77") (name "Net-(U107-SW)") (class "Default")
      (node (ref "D105") (pin "A") (pinfunction "A_A") (pintype "passive"))
      (node (ref "L102") (pin "2") (pinfunction "2_2") (pintype "passive"))
      (node (ref "U107") (pin "1") (pinfunction "SW_1") (pintype "input"))
    )
    (net (code "78") (name "Net-(U200-+)") (class "Default")
      (node (ref "J106") (pin "19") (pinfunction "19_19") (pintype "passive"))
      (node (ref "U200") (pin "3") (pinfunction "+_3") (pintype "input"))
    )
    (net (code "79") (name "Net-(U200--)") (class "Default")
      (node (ref "R202") (pin "1") (pinfunction "1_1") (pintype "passive"))
      (node (ref "R203") (pin "2") (pinfunction "2_2") (pintype "passive"))
      (node (ref "U200") (pin "1") (pinfunction "-_1") (pintype "input"))
    )
    (net (code "80") (name "VCC") (class "Default")
      (node (ref "C101") (pin "1") (pinfunction "A_1") (pintype "input"))
      (node (ref "C102") (pin "1") (pinfunction "A_1") (pintype "input"))
      (node (ref "C105") (pin "2") (pinfunction "B_2") (pintype "input"))
      (node (ref "C107") (pin "1") (pinfunction "A_1") (pintype "input"))
      (node (ref "C108") (pin "1") (pinfunction "A_1") (pintype "input"))
      (node (ref "C109") (pin "1") (pinfunction "A_1") (pintype "input"))
      (node (ref "C125") (pin "1") (pinfunction "1_1") (pintype "passive"))
      (node (ref "D105") (pin "K") (pinfunction "K_K") (pintype "passive"))
      (node (ref "J105") (pin "8") (pinfunction "8_8") (pintype "passive"))
      (node (ref "R101") (pin "1") (pinfunction "A_1") (pintype "input"))
      (node (ref "R103") (pin "1") (pinfunction "A_1") (pintype "input"))
      (node (ref "R105") (pin "1") (pinfunction "A_1") (pintype "input"))
      (node (ref "R109") (pin "1") (pinfunction "A_1") (pintype "input"))
      (node (ref "R110") (pin "1") (pinfunction "A_1") (pintype "input"))
      (node (ref "R111") (pin "1") (pinfunction "A_1") (pintype "passive"))
      (node (ref "R118") (pin "1") (pinfunction "A_1") (pintype "input"))
      (node (ref "R119") (pin "1") (pinfunction "A_1") (pintype "input"))
      (node (ref "R130") (pin "2") (pinfunction "2_2") (pintype "passive"))
      (node (ref "R132") (pin "1") (pinfunction "A_1") (pintype "input"))
      (node (ref "R202") (pin "2") (pinfunction "2_2") (pintype "passive"))
      (node (ref "TP119") (pin "1") (pinfunction "TP_1") (pintype "passive"))
      (node (ref "TP123") (pin "1") (pinfunction "TP_1") (pintype "passive"))
      (node (ref "TP125") (pin "1") (pinfunction "TP_1") (pintype "passive"))
      (node (ref "U101") (pin "20") (pinfunction "Vdd_20") (pintype "input"))
      (node (ref "U102") (pin "20") (pinfunction "Vdd_20") (pintype "input"))
      (node (ref "U103") (pin "20") (pinfunction "Vdd_20") (pintype "input"))
      (node (ref "U104") (pin "16") (pinfunction "VCC_16") (pintype "passive"))
      (node (ref "U106") (pin "4") (pinfunction "VCC_4") (pintype "input"))
      (node (ref "U200") (pin "5") (pinfunction "VDD_5") (pintype "power_in"))
    )
    (net (code "81") (name "unconnected-(J106-Pad11)") (class "Default")
      (node (ref "J106") (pin "11") (pinfunction "11_11") (pintype "passive"))
    )
    (net (code "82") (name "unconnected-(J106-Pad12)") (class "Default")
      (node (ref "J106") (pin "12") (pinfunction "12_12") (pintype "passive"))
    )
    (net (code "83") (name "unconnected-(J106-Pad13)") (class "Default")
      (node (ref "J106") (pin "13") (pinfunction "13_13") (pintype "passive"))
    )
    (net (code "84") (name "unconnected-(J106-Pad14)") (class "Default")
      (node (ref "J106") (pin "14") (pinfunction "14_14") (pintype "passive"))
    )
    (net (code "85") (name "unconnected-(J106-Pad16)") (class "Default")
      (node (ref "J106") (pin "16") (pinfunction "16_16") (pintype "passive"))
    )
    (net (code "86") (name "unconnected-(J106-Pad17)") (class "Default")
      (node (ref "J106") (pin "17") (pinfunction "17_17") (pintype "passive"))
    )
    (net (code "87") (name "unconnected-(J106-Pad20)") (class "Default")
      (node (ref "J106") (pin "20") (pinfunction "20_20") (pintype "passive"))
    )
    (net (code "88") (name "unconnected-(J106-Pad21)") (class "Default")
      (node (ref "J106") (pin "21") (pinfunction "21_21") (pintype "passive"))
    )
    (net (code "89") (name "unconnected-(J106-Pad22)") (class "Default")
      (node (ref "J106") (pin "22") (pinfunction "22_22") (pintype "passive"))
    )
    (net (code "90") (name "unconnected-(J106-Pad23)") (class "Default")
      (node (ref "J106") (pin "23") (pinfunction "23_23") (pintype "passive"))
    )
    (net (code "91") (name "unconnected-(J106-Pad24)") (class "Default")
      (node (ref "J106") (pin "24") (pinfunction "24_24") (pintype "passive"))
    )
    (net (code "92") (name "unconnected-(J106-Pad25)") (class "Default")
      (node (ref "J106") (pin "25") (pinfunction "25_25") (pintype "passive"))
    )
    (net (code "93") (name "unconnected-(J106-Pad26)") (class "Default")
      (node (ref "J106") (pin "26") (pinfunction "26_26") (pintype "passive"))
    )
    (net (code "94") (name "unconnected-(J106-Pad27)") (class "Default")
      (node (ref "J106") (pin "27") (pinfunction "27_27") (pintype "passive"))
    )
    (net (code "95") (name "unconnected-(J106-Pad28)") (class "Default")
      (node (ref "J106") (pin "28") (pinfunction "28_28") (pintype "passive"))
    )
    (net (code "96") (name "unconnected-(J106-Pad29)") (class "Default")
      (node (ref "J106") (pin "29") (pinfunction "29_29") (pintype "passive"))
    )
    (net (code "97") (name "unconnected-(J106-Pad30)") (class "Default")
      (node (ref "J106") (pin "30") (pinfunction "30_30") (pintype "passive"))
    )
    (net (code "98") (name "unconnected-(J106-Pad31)") (class "Default")
      (node (ref "J106") (pin "31") (pinfunction "31_31") (pintype "passive"))
    )
    (net (code "99") (name "unconnected-(J106-Pad32)") (class "Default")
      (node (ref "J106") (pin "32") (pinfunction "32_32") (pintype "passive"))
    )
    (net (code "100") (name "unconnected-(J106-Pad33)") (class "Default")
      (node (ref "J106") (pin "33") (pinfunction "33_33") (pintype "passive"))
    )
    (net (code "101") (name "unconnected-(J106-Pad34)") (class "Default")
      (node (ref "J106") (pin "34") (pinfunction "34_34") (pintype "passive"))
    )
    (net (code "102") (name "unconnected-(J106-Pad35)") (class "Default")
      (node (ref "J106") (pin "35") (pinfunction "35_35") (pintype "passive"))
    )
    (net (code "103") (name "unconnected-(J106-Pad36)") (class "Default")
      (node (ref "J106") (pin "36") (pinfunction "36_36") (pintype "passive"))
    )
    (net (code "104") (name "unconnected-(J106-Pad37)") (class "Default")
      (node (ref "J106") (pin "37") (pinfunction "37_37") (pintype "passive"))
    )
    (net (code "105") (name "unconnected-(J106-Pad38)") (class "Default")
      (node (ref "J106") (pin "38") (pinfunction "38_38") (pintype "passive"))
    )
    (net (code "106") (name "unconnected-(J106-Pad39)") (class "Default")
      (node (ref "J106") (pin "39") (pinfunction "39_39") (pintype "passive"))
    )
    (net (code "107") (name "unconnected-(J106-Pad40)") (class "Default")
      (node (ref "J106") (pin "40") (pinfunction "40_40") (pintype "passive"))
    )
    (net (code "108") (name "unconnected-(U101-OSC2{slash}CLKOUT-Pad10)") (class "Default")
      (node (ref "U101") (pin "10") (pinfunction "OSC2/CLKOUT_10") (pintype "input"))
    )
    (net (code "109") (name "unconnected-(U101-RA5{slash}AN4-Pad7)") (class "Default")
      (node (ref "U101") (pin "7") (pinfunction "RA5/AN4_7") (pintype "input"))
    )
    (net (code "110") (name "unconnected-(U101-RB1-Pad22)") (class "Default")
      (node (ref "U101") (pin "22") (pinfunction "RB1_22") (pintype "input"))
    )
    (net (code "111") (name "unconnected-(U102-OSC2{slash}CLKOUT-Pad10)") (class "Default")
      (node (ref "U102") (pin "10") (pinfunction "OSC2/CLKOUT_10") (pintype "input"))
    )
    (net (code "112") (name "unconnected-(U103-OSC2{slash}CLKOUT-Pad10)") (class "Default")
      (node (ref "U103") (pin "10") (pinfunction "OSC2/CLKOUT_10") (pintype "input"))
    )
    (net (code "113") (name "unconnected-(U103-RC0{slash}T1OSO{slash}T1CKI-Pad11)") (class "Default")
      (node (ref "U103") (pin "11") (pinfunction "RC0/T1OSO/T1CKI_11") (pintype "input"))
    )
    (net (code "114") (name "unconnected-(U103-RC1{slash}T1OSI-Pad12)") (class "Default")
      (node (ref "U103") (pin "12") (pinfunction "RC1/T1OSI_12") (pintype "input"))
    )
    (net (code "115") (name "unconnected-(U103-RC6{slash}TX{slash}CK-Pad17)") (class "Default")
      (node (ref "U103") (pin "17") (pinfunction "RC6/TX/CK_17") (pintype "input"))
    )
    (net (code "116") (name "unconnected-(U106-OE-Pad1)") (class "Default")
      (node (ref "U106") (pin "1") (pinfunction "OE_1") (pintype "input"))
    )
  )
)
